# zumo_cam_02.net
KiCad netlist of a schematic drawn in EAGLE
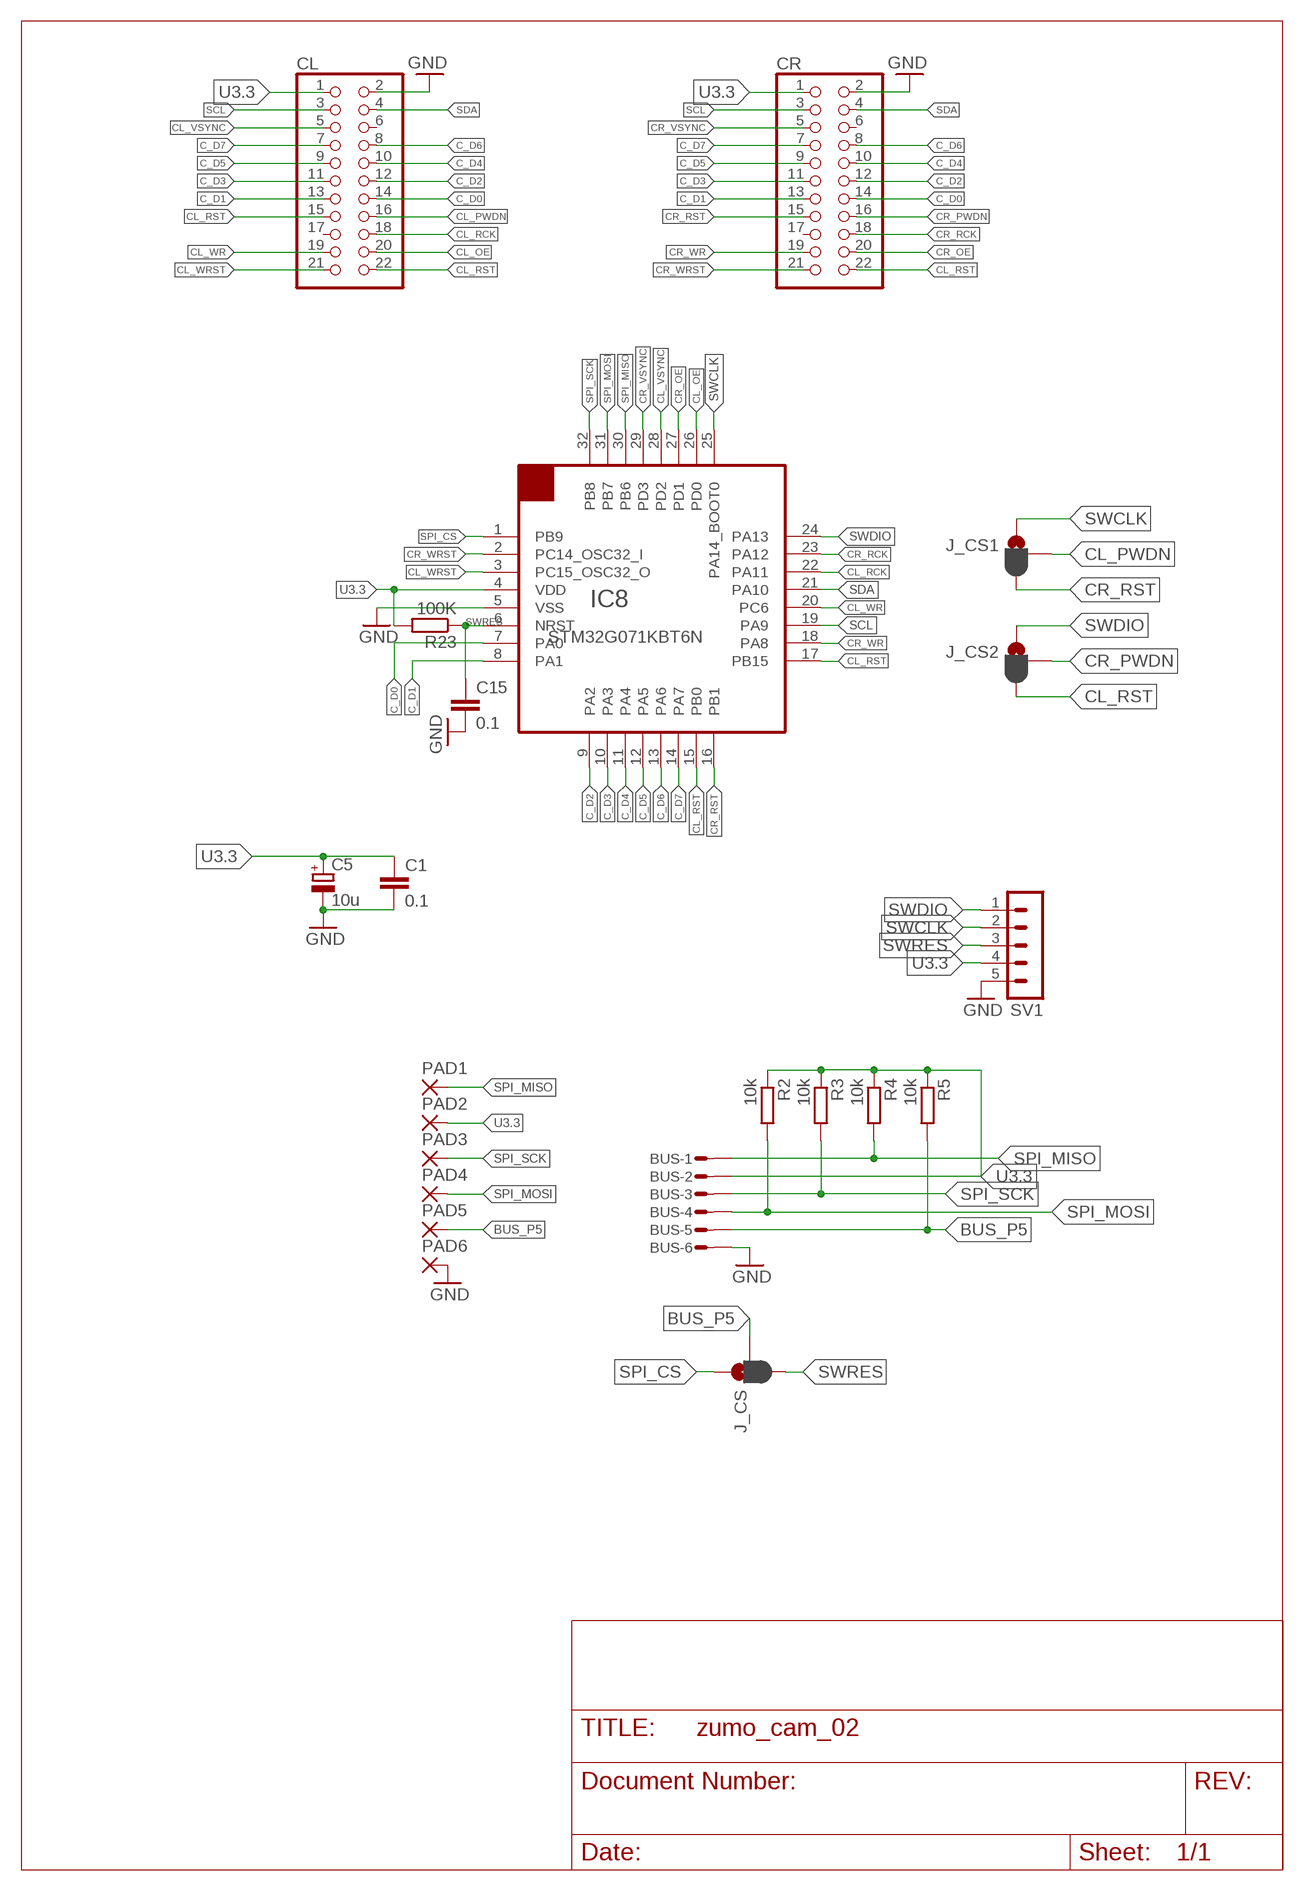
[diagram p0: schematic, sheet 1]

(export (version "E")
  (design (tool "Eeschema 10.0.6"))
  (components
    (comp (ref "BUS")
      (value "MICROMATCH-6SMD")
      (footprint "eagle-import:MICROMATCH-6SMD")
      (libsource (lib "eagle-import") (part "MICROMATCH-6SMD"))
    )
    (comp (ref "C1")
      (value "0.1")
      (footprint "eagle-import:C0805")
      (libsource (lib "eagle-import") (part "C-EUC0805"))
    )
    (comp (ref "C5")
      (value "10u")
      (footprint "eagle-import:B_3528-21W")
      (libsource (lib "eagle-import") (part "CPOL-EUB/3528-21W"))
    )
    (comp (ref "C15")
      (value "0.1")
      (footprint "eagle-import:C0805")
      (libsource (lib "eagle-import") (part "C-EUC0805"))
    )
    (comp (ref "CL")
      (value "PINHD-2X11_2.54-SMD")
      (footprint "eagle-import:2X11SMD")
      (libsource (lib "eagle-import") (part "PINHD-2X11_2.54-SMD"))
    )
    (comp (ref "CR")
      (value "PINHD-2X11_2.54-SMD")
      (footprint "eagle-import:2X11SMD")
      (libsource (lib "eagle-import") (part "PINHD-2X11_2.54-SMD"))
    )
    (comp (ref "IC8")
      (value "STM32G071KBT6N")
      (footprint "eagle-import:LQFP-32")
      (libsource (lib "eagle-import") (part "STM32G071KBT6N"))
    )
    (comp (ref "J_CS")
      (value "JUMPER-SMT_3_1-NC_PASTE_NO-SILK")
      (footprint "eagle-import:SMT-JUMPER_3_1-NC_PASTE_NO-SILK")
      (libsource (lib "eagle-import") (part "JUMPER-SMT_3_1-NC_PASTE_NO-SILK"))
    )
    (comp (ref "J_CS1")
      (value "JUMPER-SMT_3_1-NC_PASTE_NO-SILK")
      (footprint "eagle-import:SMT-JUMPER_3_1-NC_PASTE_NO-SILK")
      (libsource (lib "eagle-import") (part "JUMPER-SMT_3_1-NC_PASTE_NO-SILK"))
    )
    (comp (ref "J_CS2")
      (value "JUMPER-SMT_3_1-NC_PASTE_NO-SILK")
      (footprint "eagle-import:SMT-JUMPER_3_1-NC_PASTE_NO-SILK")
      (libsource (lib "eagle-import") (part "JUMPER-SMT_3_1-NC_PASTE_NO-SILK"))
    )
    (comp (ref "PAD1")
      (value "SMD2")
      (footprint "eagle-import:SMD1,27-2,54")
      (libsource (lib "eagle-import") (part "SMD2"))
    )
    (comp (ref "PAD2")
      (value "SMD2")
      (footprint "eagle-import:SMD1,27-2,54")
      (libsource (lib "eagle-import") (part "SMD2"))
    )
    (comp (ref "PAD3")
      (value "SMD2")
      (footprint "eagle-import:SMD1,27-2,54")
      (libsource (lib "eagle-import") (part "SMD2"))
    )
    (comp (ref "PAD4")
      (value "SMD2")
      (footprint "eagle-import:SMD1,27-2,54")
      (libsource (lib "eagle-import") (part "SMD2"))
    )
    (comp (ref "PAD5")
      (value "SMD2")
      (footprint "eagle-import:SMD1,27-2,54")
      (libsource (lib "eagle-import") (part "SMD2"))
    )
    (comp (ref "PAD6")
      (value "SMD2")
      (footprint "eagle-import:SMD1,27-2,54")
      (libsource (lib "eagle-import") (part "SMD2"))
    )
    (comp (ref "R2")
      (value "10k")
      (footprint "eagle-import:M0805")
      (libsource (lib "eagle-import") (part "rcl_334_R-EU_M0805"))
    )
    (comp (ref "R3")
      (value "10k")
      (footprint "eagle-import:M0805")
      (libsource (lib "eagle-import") (part "rcl_334_R-EU_M0805"))
    )
    (comp (ref "R4")
      (value "10k")
      (footprint "eagle-import:M0805")
      (libsource (lib "eagle-import") (part "rcl_334_R-EU_M0805"))
    )
    (comp (ref "R5")
      (value "10k")
      (footprint "eagle-import:M0805")
      (libsource (lib "eagle-import") (part "rcl_334_R-EU_M0805"))
    )
    (comp (ref "R23")
      (value "100K")
      (footprint "eagle-import:R0805")
      (libsource (lib "eagle-import") (part "R-EU_R0805"))
    )
    (comp (ref "SV1")
      (value "MA05-1")
      (footprint "eagle-import:MA05-1")
      (libsource (lib "eagle-import") (part "MA05-1"))
    )
  )
  (nets
    (net (code "1") (name "BUS_P5") (class "Default")
      (node (ref "BUS") (pin "5") (pinfunction "S_5") (pintype "passive"))
      (node (ref "J_CS") (pin "2") (pinfunction "2_2") (pintype "passive"))
      (node (ref "PAD5") (pin "1") (pinfunction "P_1") (pintype "passive"))
      (node (ref "R5") (pin "2") (pinfunction "2_2") (pintype "passive"))
    )
    (net (code "2") (name "CL_OE") (class "Default")
      (node (ref "CL") (pin "20") (pinfunction "20_20") (pintype "passive"))
      (node (ref "IC8") (pin "26") (pinfunction "PD0_26") (pintype "bidirectional"))
    )
    (net (code "3") (name "CL_PWDN") (class "Default")
      (node (ref "CL") (pin "16") (pinfunction "16_16") (pintype "passive"))
      (node (ref "J_CS1") (pin "2") (pinfunction "2_2") (pintype "passive"))
    )
    (net (code "4") (name "CL_RCK") (class "Default")
      (node (ref "CL") (pin "18") (pinfunction "18_18") (pintype "passive"))
      (node (ref "IC8") (pin "22") (pinfunction "PA11_22") (pintype "bidirectional"))
    )
    (net (code "5") (name "CL_RST") (class "Default")
      (node (ref "CL") (pin "15") (pinfunction "15_15") (pintype "passive"))
      (node (ref "CL") (pin "22") (pinfunction "22_22") (pintype "passive"))
      (node (ref "CR") (pin "22") (pinfunction "22_22") (pintype "passive"))
      (node (ref "IC8") (pin "15") (pinfunction "PB0_15") (pintype "bidirectional"))
      (node (ref "IC8") (pin "17") (pinfunction "PB15_17") (pintype "bidirectional"))
      (node (ref "J_CS2") (pin "3") (pinfunction "3_3") (pintype "passive"))
    )
    (net (code "6") (name "CL_VSYNC") (class "Default")
      (node (ref "CL") (pin "5") (pinfunction "5_5") (pintype "passive"))
      (node (ref "IC8") (pin "28") (pinfunction "PD2_28") (pintype "bidirectional"))
    )
    (net (code "7") (name "CL_WR") (class "Default")
      (node (ref "CL") (pin "19") (pinfunction "19_19") (pintype "passive"))
      (node (ref "IC8") (pin "20") (pinfunction "PC6_20") (pintype "bidirectional"))
    )
    (net (code "8") (name "CL_WRST") (class "Default")
      (node (ref "CL") (pin "21") (pinfunction "21_21") (pintype "passive"))
      (node (ref "IC8") (pin "3") (pinfunction "PC15_OSC32_O_3") (pintype "bidirectional"))
    )
    (net (code "9") (name "CR_OE") (class "Default")
      (node (ref "CR") (pin "20") (pinfunction "20_20") (pintype "passive"))
      (node (ref "IC8") (pin "27") (pinfunction "PD1_27") (pintype "bidirectional"))
    )
    (net (code "10") (name "CR_PWDN") (class "Default")
      (node (ref "CR") (pin "16") (pinfunction "16_16") (pintype "passive"))
      (node (ref "J_CS2") (pin "2") (pinfunction "2_2") (pintype "passive"))
    )
    (net (code "11") (name "CR_RCK") (class "Default")
      (node (ref "CR") (pin "18") (pinfunction "18_18") (pintype "passive"))
      (node (ref "IC8") (pin "23") (pinfunction "PA12_23") (pintype "bidirectional"))
    )
    (net (code "12") (name "CR_RST") (class "Default")
      (node (ref "CR") (pin "15") (pinfunction "15_15") (pintype "passive"))
      (node (ref "IC8") (pin "16") (pinfunction "PB1_16") (pintype "bidirectional"))
      (node (ref "J_CS1") (pin "3") (pinfunction "3_3") (pintype "passive"))
    )
    (net (code "13") (name "CR_VSYNC") (class "Default")
      (node (ref "CR") (pin "5") (pinfunction "5_5") (pintype "passive"))
      (node (ref "IC8") (pin "29") (pinfunction "PD3_29") (pintype "bidirectional"))
    )
    (net (code "14") (name "CR_WR") (class "Default")
      (node (ref "CR") (pin "19") (pinfunction "19_19") (pintype "passive"))
      (node (ref "IC8") (pin "18") (pinfunction "PA8_18") (pintype "bidirectional"))
    )
    (net (code "15") (name "CR_WRST") (class "Default")
      (node (ref "CR") (pin "21") (pinfunction "21_21") (pintype "passive"))
      (node (ref "IC8") (pin "2") (pinfunction "PC14_OSC32_I_2") (pintype "bidirectional"))
    )
    (net (code "16") (name "C_D0") (class "Default")
      (node (ref "CL") (pin "14") (pinfunction "14_14") (pintype "passive"))
      (node (ref "CR") (pin "14") (pinfunction "14_14") (pintype "passive"))
      (node (ref "IC8") (pin "7") (pinfunction "PA0_7") (pintype "bidirectional"))
    )
    (net (code "17") (name "C_D1") (class "Default")
      (node (ref "CL") (pin "13") (pinfunction "13_13") (pintype "passive"))
      (node (ref "CR") (pin "13") (pinfunction "13_13") (pintype "passive"))
      (node (ref "IC8") (pin "8") (pinfunction "PA1_8") (pintype "bidirectional"))
    )
    (net (code "18") (name "C_D2") (class "Default")
      (node (ref "CL") (pin "12") (pinfunction "12_12") (pintype "passive"))
      (node (ref "CR") (pin "12") (pinfunction "12_12") (pintype "passive"))
      (node (ref "IC8") (pin "9") (pinfunction "PA2_9") (pintype "bidirectional"))
    )
    (net (code "19") (name "C_D3") (class "Default")
      (node (ref "CL") (pin "11") (pinfunction "11_11") (pintype "passive"))
      (node (ref "CR") (pin "11") (pinfunction "11_11") (pintype "passive"))
      (node (ref "IC8") (pin "10") (pinfunction "PA3_10") (pintype "bidirectional"))
    )
    (net (code "20") (name "C_D4") (class "Default")
      (node (ref "CL") (pin "10") (pinfunction "10_10") (pintype "passive"))
      (node (ref "CR") (pin "10") (pinfunction "10_10") (pintype "passive"))
      (node (ref "IC8") (pin "11") (pinfunction "PA4_11") (pintype "bidirectional"))
    )
    (net (code "21") (name "C_D5") (class "Default")
      (node (ref "CL") (pin "9") (pinfunction "9_9") (pintype "passive"))
      (node (ref "CR") (pin "9") (pinfunction "9_9") (pintype "passive"))
      (node (ref "IC8") (pin "12") (pinfunction "PA5_12") (pintype "bidirectional"))
    )
    (net (code "22") (name "C_D6") (class "Default")
      (node (ref "CL") (pin "8") (pinfunction "8_8") (pintype "passive"))
      (node (ref "CR") (pin "8") (pinfunction "8_8") (pintype "passive"))
      (node (ref "IC8") (pin "13") (pinfunction "PA6_13") (pintype "bidirectional"))
    )
    (net (code "23") (name "C_D7") (class "Default")
      (node (ref "CL") (pin "7") (pinfunction "7_7") (pintype "passive"))
      (node (ref "CR") (pin "7") (pinfunction "7_7") (pintype "passive"))
      (node (ref "IC8") (pin "14") (pinfunction "PA7_14") (pintype "bidirectional"))
    )
    (net (code "24") (name "GND") (class "Default")
      (node (ref "BUS") (pin "6") (pinfunction "S_6") (pintype "passive"))
      (node (ref "C1") (pin "2") (pinfunction "2_2") (pintype "passive"))
      (node (ref "C15") (pin "2") (pinfunction "2_2") (pintype "passive"))
      (node (ref "C5") (pin "-") (pinfunction "-_-") (pintype "passive"))
      (node (ref "CL") (pin "2") (pinfunction "2_2") (pintype "passive"))
      (node (ref "CR") (pin "2") (pinfunction "2_2") (pintype "passive"))
      (node (ref "IC8") (pin "5") (pinfunction "VSS_5") (pintype "power_in"))
      (node (ref "PAD6") (pin "1") (pinfunction "P_1") (pintype "passive"))
      (node (ref "SV1") (pin "5") (pinfunction "5_5") (pintype "passive"))
    )
    (net (code "25") (name "SCL") (class "Default")
      (node (ref "CL") (pin "3") (pinfunction "3_3") (pintype "passive"))
      (node (ref "CR") (pin "3") (pinfunction "3_3") (pintype "passive"))
      (node (ref "IC8") (pin "19") (pinfunction "PA9_19") (pintype "bidirectional"))
    )
    (net (code "26") (name "SDA") (class "Default")
      (node (ref "CL") (pin "4") (pinfunction "4_4") (pintype "passive"))
      (node (ref "CR") (pin "4") (pinfunction "4_4") (pintype "passive"))
      (node (ref "IC8") (pin "21") (pinfunction "PA10_21") (pintype "bidirectional"))
    )
    (net (code "27") (name "SPI_CS") (class "Default")
      (node (ref "IC8") (pin "1") (pinfunction "PB9_1") (pintype "bidirectional"))
      (node (ref "J_CS") (pin "1") (pinfunction "1_1") (pintype "passive"))
    )
    (net (code "28") (name "SPI_MISO") (class "Default")
      (node (ref "BUS") (pin "1") (pinfunction "S_1") (pintype "passive"))
      (node (ref "IC8") (pin "30") (pinfunction "PB6_30") (pintype "bidirectional"))
      (node (ref "PAD1") (pin "1") (pinfunction "P_1") (pintype "passive"))
      (node (ref "R4") (pin "2") (pinfunction "2_2") (pintype "passive"))
    )
    (net (code "29") (name "SPI_MOSI") (class "Default")
      (node (ref "BUS") (pin "4") (pinfunction "S_4") (pintype "passive"))
      (node (ref "IC8") (pin "31") (pinfunction "PB7_31") (pintype "bidirectional"))
      (node (ref "PAD4") (pin "1") (pinfunction "P_1") (pintype "passive"))
      (node (ref "R2") (pin "2") (pinfunction "2_2") (pintype "passive"))
    )
    (net (code "30") (name "SPI_SCK") (class "Default")
      (node (ref "BUS") (pin "3") (pinfunction "S_3") (pintype "passive"))
      (node (ref "IC8") (pin "32") (pinfunction "PB8_32") (pintype "bidirectional"))
      (node (ref "PAD3") (pin "1") (pinfunction "P_1") (pintype "passive"))
      (node (ref "R3") (pin "2") (pinfunction "2_2") (pintype "passive"))
    )
    (net (code "31") (name "SWCLK") (class "Default")
      (node (ref "IC8") (pin "25") (pinfunction "PA14_BOOT0_25") (pintype "bidirectional"))
      (node (ref "J_CS1") (pin "1") (pinfunction "1_1") (pintype "passive"))
      (node (ref "SV1") (pin "2") (pinfunction "2_2") (pintype "passive"))
    )
    (net (code "32") (name "SWDIO") (class "Default")
      (node (ref "IC8") (pin "24") (pinfunction "PA13_24") (pintype "bidirectional"))
      (node (ref "J_CS2") (pin "1") (pinfunction "1_1") (pintype "passive"))
      (node (ref "SV1") (pin "1") (pinfunction "1_1") (pintype "passive"))
    )
    (net (code "33") (name "SWRES") (class "Default")
      (node (ref "C15") (pin "1") (pinfunction "1_1") (pintype "passive"))
      (node (ref "IC8") (pin "6") (pinfunction "NRST_6") (pintype "bidirectional"))
      (node (ref "J_CS") (pin "3") (pinfunction "3_3") (pintype "passive"))
      (node (ref "R23") (pin "1") (pinfunction "1_1") (pintype "passive"))
      (node (ref "SV1") (pin "3") (pinfunction "3_3") (pintype "passive"))
    )
    (net (code "34") (name "U3.3") (class "Default")
      (node (ref "BUS") (pin "2") (pinfunction "S_2") (pintype "passive"))
      (node (ref "C1") (pin "1") (pinfunction "1_1") (pintype "passive"))
      (node (ref "C5") (pin "+") (pinfunction "+_+") (pintype "passive"))
      (node (ref "CL") (pin "1") (pinfunction "1_1") (pintype "passive"))
      (node (ref "CR") (pin "1") (pinfunction "1_1") (pintype "passive"))
      (node (ref "IC8") (pin "4") (pinfunction "VDD_4") (pintype "power_in"))
      (node (ref "PAD2") (pin "1") (pinfunction "P_1") (pintype "passive"))
      (node (ref "R2") (pin "1") (pinfunction "1_1") (pintype "passive"))
      (node (ref "R23") (pin "2") (pinfunction "2_2") (pintype "passive"))
      (node (ref "R3") (pin "1") (pinfunction "1_1") (pintype "passive"))
      (node (ref "R4") (pin "1") (pinfunction "1_1") (pintype "passive"))
      (node (ref "R5") (pin "1") (pinfunction "1_1") (pintype "passive"))
      (node (ref "SV1") (pin "4") (pinfunction "4_4") (pintype "passive"))
    )
    (net (code "35") (name "unconnected-(CL-Pad6)") (class "Default")
      (node (ref "CL") (pin "6") (pinfunction "6_6") (pintype "passive"))
    )
    (net (code "36") (name "unconnected-(CL-Pad17)") (class "Default")
      (node (ref "CL") (pin "17") (pinfunction "17_17") (pintype "passive"))
    )
    (net (code "37") (name "unconnected-(CR-Pad6)") (class "Default")
      (node (ref "CR") (pin "6") (pinfunction "6_6") (pintype "passive"))
    )
    (net (code "38") (name "unconnected-(CR-Pad17)") (class "Default")
      (node (ref "CR") (pin "17") (pinfunction "17_17") (pintype "passive"))
    )
  )
)
